# H-Link.net
KiCad netlist of a schematic drawn in Altium Designer
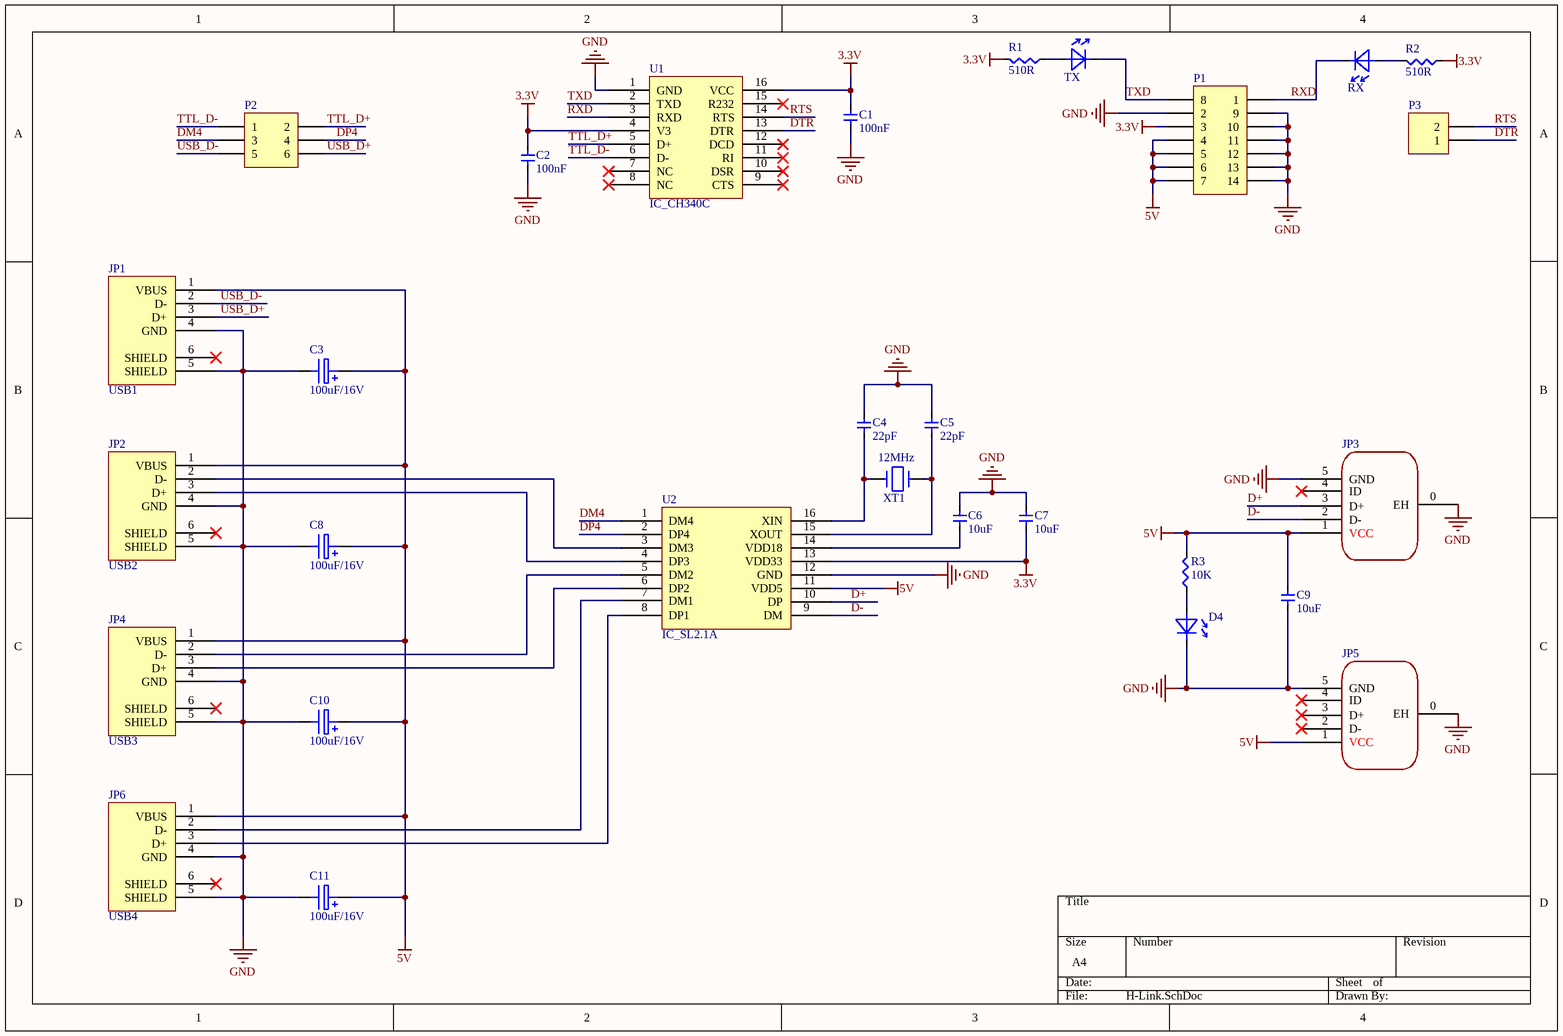
[diagram p0: H-Link.SchDoc]

(export (version "E")
  (design (tool "Eeschema 10.0.6"))
  (components
    (comp (ref "C1")
      (value "100nF")
      (footprint "C 0603_M")
      (description "电容")
      (libsource (lib "MySCHLIB") (part "CX_CAP"))
    )
    (comp (ref "C2")
      (value "100nF")
      (footprint "C 0603_M")
      (description "电容")
      (libsource (lib "MySCHLIB") (part "CX_CAP"))
    )
    (comp (ref "C3")
      (value "100uF/16V")
      (footprint "CT 6*4 - R")
      (description "电解电容")
      (libsource (lib "MySCHLIB") (part "CC_ELECTOR1"))
    )
    (comp (ref "C4")
      (value "22pF")
      (footprint "C 0603_M")
      (description "电容")
      (libsource (lib "MySCHLIB") (part "CX_CAP"))
    )
    (comp (ref "C5")
      (value "22pF")
      (footprint "C 0603_M")
      (description "电容")
      (libsource (lib "MySCHLIB") (part "CX_CAP"))
    )
    (comp (ref "C6")
      (value "10uF")
      (footprint "C 0603_M")
      (description "电容")
      (libsource (lib "MySCHLIB") (part "CX_CAP"))
    )
    (comp (ref "C7")
      (value "10uF")
      (footprint "C 0603_M")
      (description "电容")
      (libsource (lib "MySCHLIB") (part "CX_CAP"))
    )
    (comp (ref "C8")
      (value "100uF/16V")
      (footprint "CT 6*4 - R")
      (description "电解电容")
      (libsource (lib "MySCHLIB") (part "CC_ELECTOR1"))
    )
    (comp (ref "C9")
      (value "10uF")
      (footprint "C 0603_M")
      (description "电容")
      (libsource (lib "MySCHLIB") (part "CX_CAP"))
    )
    (comp (ref "C10")
      (value "100uF/16V")
      (footprint "CT 6*4 - R")
      (description "电解电容")
      (libsource (lib "MySCHLIB") (part "CC_ELECTOR1"))
    )
    (comp (ref "C11")
      (value "100uF/16V")
      (footprint "CT 6*4 - R")
      (description "电解电容")
      (libsource (lib "MySCHLIB") (part "CC_ELECTOR1"))
    )
    (comp (ref "D4")
      (value "DX_LED")
      (footprint "LED 0603G")
      (description "发光二极管")
      (libsource (lib "MySCHLIB") (part "DX_LED"))
    )
    (comp (ref "JP1")
      (value "USB1")
      (footprint "USB A SMD")
      (libsource (lib "MySCHLIB") (part "PT_USB_A_WX1"))
    )
    (comp (ref "JP2")
      (value "USB2")
      (footprint "USB A SMD")
      (libsource (lib "MySCHLIB") (part "PT_USB_A_WX1"))
    )
    (comp (ref "JP3")
      (value "PT_USB_MINI")
      (footprint "USB MINI-5P-90度弯针")
      (libsource (lib "MySCHLIB") (part "PT_USB_MINI"))
    )
    (comp (ref "JP4")
      (value "USB3")
      (footprint "USB A SMD")
      (libsource (lib "MySCHLIB") (part "PT_USB_A_WX1"))
    )
    (comp (ref "JP5")
      (value "PT_USB_MINI")
      (footprint "USB MINI-5P-90度弯针")
      (libsource (lib "MySCHLIB") (part "PT_USB_MINI"))
    )
    (comp (ref "JP6")
      (value "USB4")
      (footprint "USB A SMD")
      (libsource (lib "MySCHLIB") (part "PT_USB_A_WX1"))
    )
    (comp (ref "P1")
      (value "Header 7X2A")
      (footprint "HDR2X7_CEN")
      (description "Header, 7-Pin, Dual row")
      (fields (field (name "PUBLISHER") "Altium Limited"))
      (libsource (lib "Miscellaneous Connectors") (part "Header 7X2A"))
    )
    (comp (ref "P2")
      (value "Header 3X2")
      (footprint "HDR2X3")
      (description "Header, 3-Pin, Dual row")
      (fields (field (name "PUBLISHER") "Altium Limited"))
      (libsource (lib "Miscellaneous Connectors") (part "Header 3X2"))
    )
    (comp (ref "P3")
      (value "Header 2")
      (footprint "HDR1X2")
      (description "Header, 2-Pin")
      (fields (field (name "PUBLISHER") "Altium Limited"))
      (libsource (lib "Miscellaneous Connectors") (part "Header 2"))
    )
    (comp (ref "R1")
      (value "510R")
      (footprint "R 0603_M")
      (description "电阻")
      (libsource (lib "MySCHLIB") (part "RX_RES"))
    )
    (comp (ref "R2")
      (value "510R")
      (footprint "R 0603_M")
      (description "电阻")
      (libsource (lib "MySCHLIB") (part "RX_RES"))
    )
    (comp (ref "R3")
      (value "10K")
      (footprint "R 0603_M")
      (description "电阻")
      (libsource (lib "MySCHLIB") (part "RX_RES"))
    )
    (comp (ref "RX")
      (value "DX_LED")
      (footprint "LED 0603G")
      (description "发光二极管")
      (libsource (lib "MySCHLIB") (part "DX_LED"))
    )
    (comp (ref "TX")
      (value "DX_LED")
      (footprint "LED 0603G")
      (description "发光二极管")
      (libsource (lib "MySCHLIB") (part "DX_LED"))
    )
    (comp (ref "U1")
      (value "IC_CH340C")
      (footprint "SOP16")
      (description "USB转串口芯片，内置晶振")
      (libsource (lib "MySCHLIB") (part "IC_CH340C"))
    )
    (comp (ref "U2")
      (value "IC_SL2.1A")
      (footprint "SOP16")
      (description "USB2.0 HUB控制器")
      (libsource (lib "MySCHLIB") (part "IC_SL2.1A"))
    )
    (comp (ref "XT1")
      (value "12MHz")
      (footprint "OSC HC-49S")
      (description "2P晶振")
      (libsource (lib "MySCHLIB") (part "XT_CRYSTAL2P"))
    )
  )
  (nets
    (net (code "1") (name "/D+") (class "Default")
      (node (ref "JP3") (pin "3") (pinfunction "D+_3") (pintype "passive"))
      (node (ref "U2") (pin "10") (pinfunction "DP_10") (pintype "passive"))
    )
    (net (code "2") (name "/D-") (class "Default")
      (node (ref "JP3") (pin "2") (pinfunction "D-_2") (pintype "passive"))
      (node (ref "U2") (pin "9") (pinfunction "DM_9") (pintype "passive"))
    )
    (net (code "3") (name "/DM4") (class "Default")
      (node (ref "P2") (pin "3") (pinfunction "3_3") (pintype "passive"))
      (node (ref "U2") (pin "1") (pinfunction "DM4_1") (pintype "passive"))
    )
    (net (code "4") (name "/DP4") (class "Default")
      (node (ref "P2") (pin "4") (pinfunction "4_4") (pintype "passive"))
      (node (ref "U2") (pin "2") (pinfunction "DP4_2") (pintype "passive"))
    )
    (net (code "5") (name "/DTR") (class "Default")
      (node (ref "P3") (pin "1") (pinfunction "1_1") (pintype "passive"))
      (node (ref "U1") (pin "13") (pinfunction "DTR_13") (pintype "passive"))
    )
    (net (code "6") (name "/RTS") (class "Default")
      (node (ref "P3") (pin "2") (pinfunction "2_2") (pintype "passive"))
      (node (ref "U1") (pin "14") (pinfunction "RTS_14") (pintype "passive"))
    )
    (net (code "7") (name "/RXD") (class "Default")
      (node (ref "P1") (pin "1") (pinfunction "1_1") (pintype "passive"))
      (node (ref "RX") (pin "K") (pinfunction "K_K") (pintype "passive"))
      (node (ref "U1") (pin "3") (pinfunction "RXD_3") (pintype "passive"))
    )
    (net (code "8") (name "/TTL_D+") (class "Default")
      (node (ref "P2") (pin "2") (pinfunction "2_2") (pintype "passive"))
      (node (ref "U1") (pin "5") (pinfunction "D+_5") (pintype "passive"))
    )
    (net (code "9") (name "/TTL_D-") (class "Default")
      (node (ref "P2") (pin "1") (pinfunction "1_1") (pintype "passive"))
      (node (ref "U1") (pin "6") (pinfunction "D-_6") (pintype "passive"))
    )
    (net (code "10") (name "/TXD") (class "Default")
      (node (ref "P1") (pin "8") (pinfunction "8_8") (pintype "passive"))
      (node (ref "TX") (pin "K") (pinfunction "K_K") (pintype "passive"))
      (node (ref "U1") (pin "2") (pinfunction "TXD_2") (pintype "passive"))
    )
    (net (code "11") (name "/USB_D+") (class "Default")
      (node (ref "JP1") (pin "3") (pinfunction "D+_3") (pintype "passive"))
      (node (ref "P2") (pin "6") (pinfunction "6_6") (pintype "passive"))
    )
    (net (code "12") (name "/USB_D-") (class "Default")
      (node (ref "JP1") (pin "2") (pinfunction "D-_2") (pintype "passive"))
      (node (ref "P2") (pin "5") (pinfunction "5_5") (pintype "passive"))
    )
    (net (code "13") (name "3.3V") (class "Default")
      (node (ref "C1") (pin "2") (pinfunction "2_2") (pintype "passive"))
      (node (ref "C2") (pin "2") (pinfunction "2_2") (pintype "passive"))
      (node (ref "C7") (pin "1") (pinfunction "1_1") (pintype "passive"))
      (node (ref "P1") (pin "3") (pinfunction "3_3") (pintype "passive"))
      (node (ref "R1") (pin "2") (pinfunction "2_2") (pintype "passive"))
      (node (ref "R2") (pin "1") (pinfunction "1_1") (pintype "passive"))
      (node (ref "U1") (pin "16") (pinfunction "VCC_16") (pintype "passive"))
      (node (ref "U1") (pin "4") (pinfunction "V3_4") (pintype "passive"))
      (node (ref "U2") (pin "13") (pinfunction "VDD33_13") (pintype "passive"))
    )
    (net (code "14") (name "5V") (class "Default")
      (node (ref "C10") (pin "1") (pinfunction "+_1") (pintype "passive"))
      (node (ref "C11") (pin "1") (pinfunction "+_1") (pintype "passive"))
      (node (ref "C3") (pin "1") (pinfunction "+_1") (pintype "passive"))
      (node (ref "C8") (pin "1") (pinfunction "+_1") (pintype "passive"))
      (node (ref "C9") (pin "2") (pinfunction "2_2") (pintype "passive"))
      (node (ref "JP1") (pin "1") (pinfunction "VBUS_1") (pintype "passive"))
      (node (ref "JP2") (pin "1") (pinfunction "VBUS_1") (pintype "passive"))
      (node (ref "JP3") (pin "1") (pinfunction "VCC_1") (pintype "passive"))
      (node (ref "JP4") (pin "1") (pinfunction "VBUS_1") (pintype "passive"))
      (node (ref "JP5") (pin "1") (pinfunction "VCC_1") (pintype "passive"))
      (node (ref "JP6") (pin "1") (pinfunction "VBUS_1") (pintype "passive"))
      (node (ref "P1") (pin "4") (pinfunction "4_4") (pintype "passive"))
      (node (ref "P1") (pin "5") (pinfunction "5_5") (pintype "passive"))
      (node (ref "P1") (pin "6") (pinfunction "6_6") (pintype "passive"))
      (node (ref "P1") (pin "7") (pinfunction "7_7") (pintype "passive"))
      (node (ref "R3") (pin "2") (pinfunction "2_2") (pintype "passive"))
      (node (ref "U2") (pin "11") (pinfunction "VDD5_11") (pintype "passive"))
    )
    (net (code "15") (name "GND") (class "Default")
      (node (ref "C1") (pin "1") (pinfunction "1_1") (pintype "passive"))
      (node (ref "C10") (pin "2") (pinfunction "-_2") (pintype "passive"))
      (node (ref "C11") (pin "2") (pinfunction "-_2") (pintype "passive"))
      (node (ref "C2") (pin "1") (pinfunction "1_1") (pintype "passive"))
      (node (ref "C3") (pin "2") (pinfunction "-_2") (pintype "passive"))
      (node (ref "C4") (pin "2") (pinfunction "2_2") (pintype "passive"))
      (node (ref "C5") (pin "2") (pinfunction "2_2") (pintype "passive"))
      (node (ref "C6") (pin "2") (pinfunction "2_2") (pintype "passive"))
      (node (ref "C7") (pin "2") (pinfunction "2_2") (pintype "passive"))
      (node (ref "C8") (pin "2") (pinfunction "-_2") (pintype "passive"))
      (node (ref "C9") (pin "1") (pinfunction "1_1") (pintype "passive"))
      (node (ref "D4") (pin "K") (pinfunction "K_K") (pintype "passive"))
      (node (ref "JP1") (pin "4") (pinfunction "GND_4") (pintype "passive"))
      (node (ref "JP1") (pin "5") (pinfunction "SHIELD_5") (pintype "passive"))
      (node (ref "JP2") (pin "4") (pinfunction "GND_4") (pintype "passive"))
      (node (ref "JP2") (pin "5") (pinfunction "SHIELD_5") (pintype "passive"))
      (node (ref "JP3") (pin "0") (pinfunction "EH_0") (pintype "passive"))
      (node (ref "JP3") (pin "5") (pinfunction "GND_5") (pintype "passive"))
      (node (ref "JP4") (pin "4") (pinfunction "GND_4") (pintype "passive"))
      (node (ref "JP4") (pin "5") (pinfunction "SHIELD_5") (pintype "passive"))
      (node (ref "JP5") (pin "0") (pinfunction "EH_0") (pintype "passive"))
      (node (ref "JP5") (pin "5") (pinfunction "GND_5") (pintype "passive"))
      (node (ref "JP6") (pin "4") (pinfunction "GND_4") (pintype "passive"))
      (node (ref "JP6") (pin "5") (pinfunction "SHIELD_5") (pintype "passive"))
      (node (ref "P1") (pin "10") (pinfunction "10_10") (pintype "passive"))
      (node (ref "P1") (pin "11") (pinfunction "11_11") (pintype "passive"))
      (node (ref "P1") (pin "12") (pinfunction "12_12") (pintype "passive"))
      (node (ref "P1") (pin "13") (pinfunction "13_13") (pintype "passive"))
      (node (ref "P1") (pin "14") (pinfunction "14_14") (pintype "passive"))
      (node (ref "P1") (pin "2") (pinfunction "2_2") (pintype "passive"))
      (node (ref "P1") (pin "9") (pinfunction "9_9") (pintype "passive"))
      (node (ref "U1") (pin "1") (pinfunction "GND_1") (pintype "passive"))
      (node (ref "U2") (pin "12") (pinfunction "GND_12") (pintype "passive"))
    )
    (net (code "16") (name "Net-(D4-PadA)") (class "Default")
      (node (ref "D4") (pin "A") (pinfunction "A_A") (pintype "passive"))
      (node (ref "R3") (pin "1") (pinfunction "1_1") (pintype "passive"))
    )
    (net (code "17") (name "Net-(JP2-D+)") (class "Default")
      (node (ref "JP2") (pin "3") (pinfunction "D+_3") (pintype "passive"))
      (node (ref "U2") (pin "4") (pinfunction "DP3_4") (pintype "passive"))
    )
    (net (code "18") (name "Net-(JP2-D-)") (class "Default")
      (node (ref "JP2") (pin "2") (pinfunction "D-_2") (pintype "passive"))
      (node (ref "U2") (pin "3") (pinfunction "DM3_3") (pintype "passive"))
    )
    (net (code "19") (name "Net-(JP4-D+)") (class "Default")
      (node (ref "JP4") (pin "3") (pinfunction "D+_3") (pintype "passive"))
      (node (ref "U2") (pin "6") (pinfunction "DP2_6") (pintype "passive"))
    )
    (net (code "20") (name "Net-(JP4-D-)") (class "Default")
      (node (ref "JP4") (pin "2") (pinfunction "D-_2") (pintype "passive"))
      (node (ref "U2") (pin "5") (pinfunction "DM2_5") (pintype "passive"))
    )
    (net (code "21") (name "Net-(JP6-D+)") (class "Default")
      (node (ref "JP6") (pin "3") (pinfunction "D+_3") (pintype "passive"))
      (node (ref "U2") (pin "8") (pinfunction "DP1_8") (pintype "passive"))
    )
    (net (code "22") (name "Net-(JP6-D-)") (class "Default")
      (node (ref "JP6") (pin "2") (pinfunction "D-_2") (pintype "passive"))
      (node (ref "U2") (pin "7") (pinfunction "DM1_7") (pintype "passive"))
    )
    (net (code "23") (name "Net-(R1-Pad1)") (class "Default")
      (node (ref "R1") (pin "1") (pinfunction "1_1") (pintype "passive"))
      (node (ref "TX") (pin "A") (pinfunction "A_A") (pintype "passive"))
    )
    (net (code "24") (name "Net-(R2-Pad2)") (class "Default")
      (node (ref "R2") (pin "2") (pinfunction "2_2") (pintype "passive"))
      (node (ref "RX") (pin "A") (pinfunction "A_A") (pintype "passive"))
    )
    (net (code "25") (name "Net-(U2-VDD18)") (class "Default")
      (node (ref "C6") (pin "1") (pinfunction "1_1") (pintype "passive"))
      (node (ref "U2") (pin "14") (pinfunction "VDD18_14") (pintype "passive"))
    )
    (net (code "26") (name "Net-(U2-XIN)") (class "Default")
      (node (ref "C4") (pin "1") (pinfunction "1_1") (pintype "passive"))
      (node (ref "U2") (pin "16") (pinfunction "XIN_16") (pintype "passive"))
      (node (ref "XT1") (pin "2") (pinfunction "2_2") (pintype "passive"))
    )
    (net (code "27") (name "Net-(U2-XOUT)") (class "Default")
      (node (ref "C5") (pin "1") (pinfunction "1_1") (pintype "passive"))
      (node (ref "U2") (pin "15") (pinfunction "XOUT_15") (pintype "passive"))
      (node (ref "XT1") (pin "1") (pinfunction "1_1") (pintype "passive"))
    )
    (net (code "28") (name "unconnected-(JP1-SHIELD-Pad6)") (class "Default")
      (node (ref "JP1") (pin "6") (pinfunction "SHIELD_6") (pintype "passive+no_connect"))
    )
    (net (code "29") (name "unconnected-(JP2-SHIELD-Pad6)") (class "Default")
      (node (ref "JP2") (pin "6") (pinfunction "SHIELD_6") (pintype "passive+no_connect"))
    )
    (net (code "30") (name "unconnected-(JP3-ID-Pad4)") (class "Default")
      (node (ref "JP3") (pin "4") (pinfunction "ID_4") (pintype "passive+no_connect"))
    )
    (net (code "31") (name "unconnected-(JP4-SHIELD-Pad6)") (class "Default")
      (node (ref "JP4") (pin "6") (pinfunction "SHIELD_6") (pintype "passive+no_connect"))
    )
    (net (code "32") (name "unconnected-(JP5-D+-Pad3)") (class "Default")
      (node (ref "JP5") (pin "3") (pinfunction "D+_3") (pintype "passive+no_connect"))
    )
    (net (code "33") (name "unconnected-(JP5-D--Pad2)") (class "Default")
      (node (ref "JP5") (pin "2") (pinfunction "D-_2") (pintype "passive+no_connect"))
    )
    (net (code "34") (name "unconnected-(JP5-ID-Pad4)") (class "Default")
      (node (ref "JP5") (pin "4") (pinfunction "ID_4") (pintype "passive+no_connect"))
    )
    (net (code "35") (name "unconnected-(JP6-SHIELD-Pad6)") (class "Default")
      (node (ref "JP6") (pin "6") (pinfunction "SHIELD_6") (pintype "passive+no_connect"))
    )
    (net (code "36") (name "unconnected-(U1-CTS-Pad9)") (class "Default")
      (node (ref "U1") (pin "9") (pinfunction "CTS_9") (pintype "passive+no_connect"))
    )
    (net (code "37") (name "unconnected-(U1-DCD-Pad12)") (class "Default")
      (node (ref "U1") (pin "12") (pinfunction "DCD_12") (pintype "passive+no_connect"))
    )
    (net (code "38") (name "unconnected-(U1-DSR-Pad10)") (class "Default")
      (node (ref "U1") (pin "10") (pinfunction "DSR_10") (pintype "passive+no_connect"))
    )
    (net (code "39") (name "unconnected-(U1-NC-Pad7)") (class "Default")
      (node (ref "U1") (pin "7") (pinfunction "NC_7") (pintype "passive+no_connect"))
    )
    (net (code "40") (name "unconnected-(U1-NC-Pad8)") (class "Default")
      (node (ref "U1") (pin "8") (pinfunction "NC_8") (pintype "passive+no_connect"))
    )
    (net (code "41") (name "unconnected-(U1-R232-Pad15)") (class "Default")
      (node (ref "U1") (pin "15") (pinfunction "R232_15") (pintype "passive+no_connect"))
    )
    (net (code "42") (name "unconnected-(U1-RI-Pad11)") (class "Default")
      (node (ref "U1") (pin "11") (pinfunction "RI_11") (pintype "passive+no_connect"))
    )
  )
)
